# G1Tech_PowerRelayMOV_v08.net
KiCad netlist of a schematic drawn in EAGLE
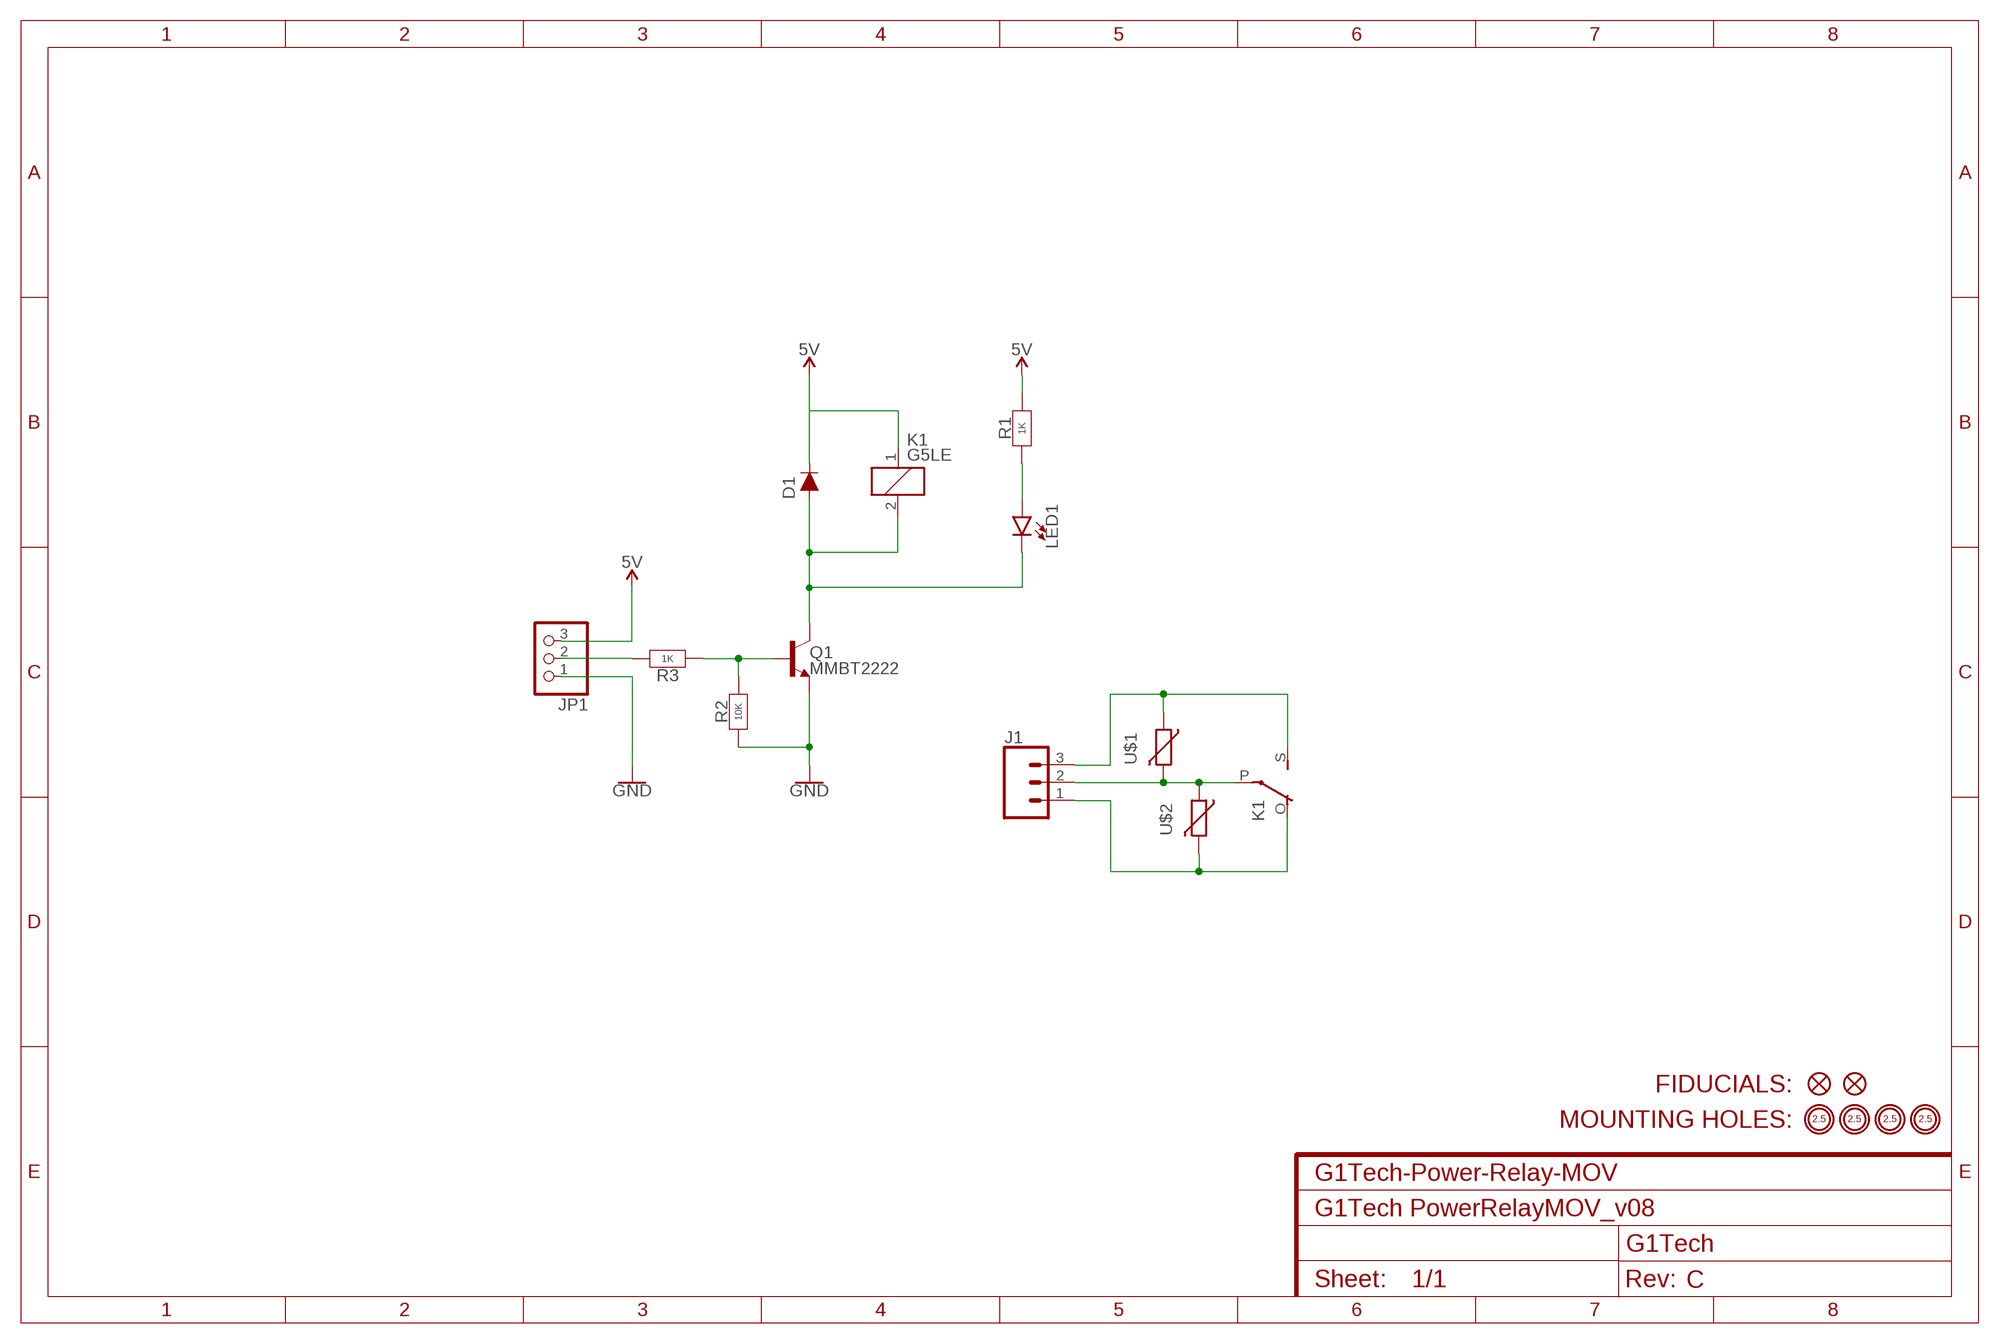
[diagram p0: schematic, sheet 1]

(export (version "E")
  (design (tool "Eeschema 10.0.6"))
  (components
    (comp (ref "D1")
      (value "DIODE-1N4148W")
      (footprint "eagle-import:SOD123")
      (libsource (lib "eagle-import") (part "DIODE-1N4148W"))
    )
    (comp (ref "FD1")
      (value "FIDUCIAL-1X2")
      (footprint "eagle-import:FIDUCIAL-1X2")
      (libsource (lib "eagle-import") (part "FIDUCIAL-1X2"))
    )
    (comp (ref "FD2")
      (value "FIDUCIAL-1X2")
      (footprint "eagle-import:FIDUCIAL-1X2")
      (libsource (lib "eagle-import") (part "FIDUCIAL-1X2"))
    )
    (comp (ref "H1")
      (value "MOUNTINGHOLE-PLATED-2.5")
      (footprint "eagle-import:MOUNTINGHOLE-PLATED-2.5")
      (libsource (lib "eagle-import") (part "MOUNTINGHOLE-PLATED-2.5"))
    )
    (comp (ref "H2")
      (value "MOUNTINGHOLE-PLATED-2.5")
      (footprint "eagle-import:MOUNTINGHOLE-PLATED-2.5")
      (libsource (lib "eagle-import") (part "MOUNTINGHOLE-PLATED-2.5"))
    )
    (comp (ref "H3")
      (value "MOUNTINGHOLE-PLATED-2.5")
      (footprint "eagle-import:MOUNTINGHOLE-PLATED-2.5")
      (libsource (lib "eagle-import") (part "MOUNTINGHOLE-PLATED-2.5"))
    )
    (comp (ref "H4")
      (value "MOUNTINGHOLE-PLATED-2.5")
      (footprint "eagle-import:MOUNTINGHOLE-PLATED-2.5")
      (libsource (lib "eagle-import") (part "MOUNTINGHOLE-PLATED-2.5"))
    )
    (comp (ref "J1")
      (value "CONN_03-SCREW-5MM")
      (footprint "eagle-import:SCREWTERMINAL-5MM-3")
      (libsource (lib "eagle-import") (part "CONN_03-SCREW-5MM"))
    )
    (comp (ref "JP1")
      (value "PINHD-1X3")
      (footprint "eagle-import:1X03")
      (libsource (lib "eagle-import") (part "PINHD-1X3"))
    )
    (comp (ref "K1")
      (value "G5LE")
      (footprint "eagle-import:G5LE")
      (libsource (lib "eagle-import") (part "G5LE"))
    )
    (comp (ref "LED1")
      (value "LED0805")
      (footprint "eagle-import:LED0805")
      (libsource (lib "eagle-import") (part "LED0805"))
    )
    (comp (ref "Q1")
      (value "MMBT2222")
      (footprint "eagle-import:SOT23-3")
      (libsource (lib "eagle-import") (part "TRANS-NPN-MMBT2222"))
    )
    (comp (ref "R1")
      (value "1K")
      (footprint "eagle-import:YAGEO-R0603")
      (libsource (lib "eagle-import") (part "YAGEO-R0603"))
    )
    (comp (ref "R2")
      (value "10K")
      (footprint "eagle-import:YAGEO-R0603")
      (libsource (lib "eagle-import") (part "YAGEO-R0603"))
    )
    (comp (ref "R3")
      (value "1K")
      (footprint "eagle-import:YAGEO-R0603")
      (libsource (lib "eagle-import") (part "YAGEO-R0603"))
    )
    (comp (ref "U$1")
      (value "MOV-V250LA4P")
      (footprint "eagle-import:V250LA4P")
      (libsource (lib "eagle-import") (part "MOV-V250LA4P"))
    )
    (comp (ref "U$2")
      (value "MOV-V250LA4P")
      (footprint "eagle-import:V250LA4P")
      (libsource (lib "eagle-import") (part "MOV-V250LA4P"))
    )
  )
  (nets
    (net (code "1") (name "5V") (class "Default")
      (node (ref "D1") (pin "C") (pinfunction "C_C") (pintype "passive"))
      (node (ref "JP1") (pin "3") (pinfunction "3_3") (pintype "passive"))
      (node (ref "K1") (pin "1") (pinfunction "1_1") (pintype "passive"))
      (node (ref "R1") (pin "2") (pinfunction "2_2") (pintype "passive"))
    )
    (net (code "2") (name "GND") (class "Default")
      (node (ref "JP1") (pin "1") (pinfunction "1_1") (pintype "passive"))
      (node (ref "Q1") (pin "2") (pinfunction "E_2") (pintype "passive"))
      (node (ref "R2") (pin "1") (pinfunction "1_1") (pintype "passive"))
    )
    (net (code "3") (name "Net-(JP1-Pad2)") (class "Default")
      (node (ref "JP1") (pin "2") (pinfunction "2_2") (pintype "passive"))
      (node (ref "R3") (pin "2") (pinfunction "2_2") (pintype "passive"))
    )
    (net (code "4") (name "Net-(LED1-PadA)") (class "Default")
      (node (ref "LED1") (pin "A") (pinfunction "A_A") (pintype "passive"))
      (node (ref "R1") (pin "1") (pinfunction "1_1") (pintype "passive"))
    )
    (net (code "5") (name "Net-(Q1-B)") (class "Default")
      (node (ref "Q1") (pin "1") (pinfunction "B_1") (pintype "passive"))
      (node (ref "R2") (pin "2") (pinfunction "2_2") (pintype "passive"))
      (node (ref "R3") (pin "1") (pinfunction "1_1") (pintype "passive"))
    )
    (net (code "6") (name "Net-(Q1-C)") (class "Default")
      (node (ref "D1") (pin "A") (pinfunction "A_A") (pintype "passive"))
      (node (ref "K1") (pin "2") (pinfunction "2_2") (pintype "passive"))
      (node (ref "LED1") (pin "C") (pinfunction "C_C") (pintype "passive"))
      (node (ref "Q1") (pin "3") (pinfunction "C_3") (pintype "passive"))
    )
    (net (code "7") (name "Net-(U$1-1)") (class "Default")
      (node (ref "J1") (pin "3") (pinfunction "3_3") (pintype "passive"))
      (node (ref "K1") (pin "S") (pinfunction "S_S") (pintype "passive"))
      (node (ref "U$1") (pin "P$1") (pinfunction "1_P$1") (pintype "passive"))
    )
    (net (code "8") (name "Net-(U$1-2)") (class "Default")
      (node (ref "J1") (pin "2") (pinfunction "2_2") (pintype "passive"))
      (node (ref "K1") (pin "P") (pinfunction "P_P") (pintype "passive"))
      (node (ref "U$1") (pin "P$2") (pinfunction "2_P$2") (pintype "passive"))
      (node (ref "U$2") (pin "P$1") (pinfunction "1_P$1") (pintype "passive"))
    )
    (net (code "9") (name "Net-(U$2-2)") (class "Default")
      (node (ref "J1") (pin "1") (pinfunction "1_1") (pintype "passive"))
      (node (ref "K1") (pin "O") (pinfunction "O_O") (pintype "passive"))
      (node (ref "U$2") (pin "P$2") (pinfunction "2_P$2") (pintype "passive"))
    )
  )
)
